# minimumSystem_Gustina_diah.net
KiCad netlist of a schematic drawn in EAGLE
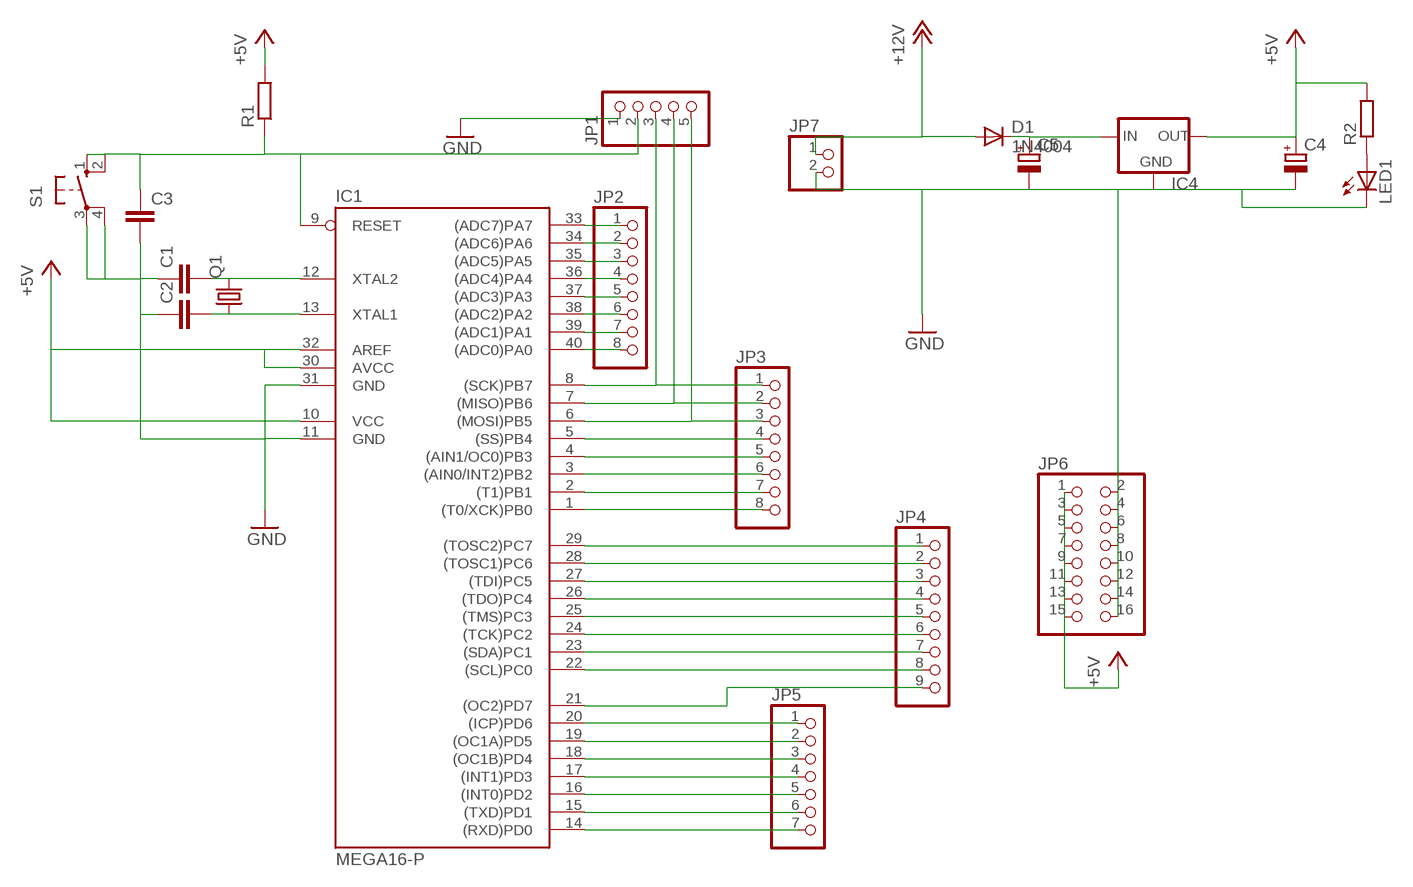
[diagram p0: schematic, sheet 1]

(export (version "E")
  (design (tool "Eeschema 10.0.6"))
  (components
    (comp (ref "C1")
      (value "C-EU025-024X044")
      (footprint "eagle-import:C025-024X044")
      (libsource (lib "eagle-import") (part "C-EU025-024X044"))
    )
    (comp (ref "C2")
      (value "C-EU025-024X044")
      (footprint "eagle-import:C025-024X044")
      (libsource (lib "eagle-import") (part "C-EU025-024X044"))
    )
    (comp (ref "C3")
      (value "C-EU050-025X075")
      (footprint "eagle-import:C050-025X075")
      (libsource (lib "eagle-import") (part "resistor_C-EU050-025X075"))
    )
    (comp (ref "C4")
      (value "CPOL-EUE2.5-5")
      (footprint "eagle-import:E2,5-5")
      (libsource (lib "eagle-import") (part "CPOL-EUE2.5-5"))
    )
    (comp (ref "C5")
      (value "CPOL-EUE2.5-5")
      (footprint "eagle-import:E2,5-5")
      (libsource (lib "eagle-import") (part "CPOL-EUE2.5-5"))
    )
    (comp (ref "D1")
      (value "1N4004")
      (footprint "eagle-import:DO41-10")
      (libsource (lib "eagle-import") (part "1N4004"))
    )
    (comp (ref "IC1")
      (value "MEGA16-P")
      (footprint "eagle-import:DIL40")
      (fields (field (name "MPN") "ATMEGA16-16PU"))
      (libsource (lib "eagle-import") (part "MEGA16-P"))
    )
    (comp (ref "IC4")
      (value "78XXS")
      (footprint "eagle-import:78XXS")
      (libsource (lib "eagle-import") (part "78XXS"))
    )
    (comp (ref "JP1")
      (value "PINHD-1X5")
      (footprint "eagle-import:1X05")
      (libsource (lib "eagle-import") (part "PINHD-1X5"))
    )
    (comp (ref "JP2")
      (value "PINHD-1X8")
      (footprint "eagle-import:1X08")
      (libsource (lib "eagle-import") (part "PINHD-1X8"))
    )
    (comp (ref "JP3")
      (value "PINHD-1X8")
      (footprint "eagle-import:1X08")
      (libsource (lib "eagle-import") (part "PINHD-1X8"))
    )
    (comp (ref "JP4")
      (value "PINHD-1X9")
      (footprint "eagle-import:1X09")
      (libsource (lib "eagle-import") (part "PINHD-1X9"))
    )
    (comp (ref "JP5")
      (value "PINHD-1X7")
      (footprint "eagle-import:1X07")
      (libsource (lib "eagle-import") (part "PINHD-1X7"))
    )
    (comp (ref "JP6")
      (value "PINHD-2X8")
      (footprint "eagle-import:2X08")
      (libsource (lib "eagle-import") (part "PINHD-2X8"))
    )
    (comp (ref "JP7")
      (value "PINHD-1X2")
      (footprint "eagle-import:1X02")
      (libsource (lib "eagle-import") (part "PINHD-1X2"))
    )
    (comp (ref "LED1")
      (value "LED5MM")
      (footprint "eagle-import:LED5MM")
      (libsource (lib "eagle-import") (part "LED5MM"))
    )
    (comp (ref "Q1")
      (value "CRYSTALHC49U-V")
      (footprint "eagle-import:HC49U-V")
      (libsource (lib "eagle-import") (part "CRYSTALHC49U-V"))
    )
    (comp (ref "R1")
      (value "R-EU_0204/7")
      (footprint "eagle-import:0204_7")
      (libsource (lib "eagle-import") (part "R-EU_0204/7"))
    )
    (comp (ref "R2")
      (value "R-EU_0204/7")
      (footprint "eagle-import:0204_7")
      (libsource (lib "eagle-import") (part "R-EU_0204/7"))
    )
    (comp (ref "S1")
      (value "10-XX")
      (footprint "eagle-import:B3F-10XX")
      (fields (field (name "MPN") "B3F-1000"))
      (libsource (lib "eagle-import") (part "10-XX"))
    )
  )
  (nets
    (net (code "1") (name "+5V") (class "Default")
      (node (ref "C4") (pin "+") (pinfunction "+_+") (pintype "passive"))
      (node (ref "IC1") (pin "10") (pinfunction "VCC_10") (pintype "power_in"))
      (node (ref "IC1") (pin "30") (pinfunction "AVCC_30") (pintype "power_in"))
      (node (ref "IC1") (pin "32") (pinfunction "AREF_32") (pintype "passive"))
      (node (ref "IC4") (pin "OUT") (pinfunction "OUT_OUT") (pintype "passive"))
      (node (ref "JP6") (pin "1") (pinfunction "1_1") (pintype "passive"))
      (node (ref "JP6") (pin "11") (pinfunction "11_11") (pintype "passive"))
      (node (ref "JP6") (pin "13") (pinfunction "13_13") (pintype "passive"))
      (node (ref "JP6") (pin "15") (pinfunction "15_15") (pintype "passive"))
      (node (ref "JP6") (pin "3") (pinfunction "3_3") (pintype "passive"))
      (node (ref "JP6") (pin "5") (pinfunction "5_5") (pintype "passive"))
      (node (ref "JP6") (pin "7") (pinfunction "7_7") (pintype "passive"))
      (node (ref "JP6") (pin "9") (pinfunction "9_9") (pintype "passive"))
      (node (ref "R1") (pin "2") (pinfunction "2_2") (pintype "passive"))
      (node (ref "R2") (pin "2") (pinfunction "2_2") (pintype "passive"))
    )
    (net (code "2") (name "+12V") (class "Default")
      (node (ref "D1") (pin "A") (pinfunction "A_A") (pintype "passive"))
      (node (ref "JP7") (pin "1") (pinfunction "1_1") (pintype "passive"))
    )
    (net (code "3") (name "GND") (class "Default")
      (node (ref "C1") (pin "1") (pinfunction "1_1") (pintype "passive"))
      (node (ref "C2") (pin "1") (pinfunction "1_1") (pintype "passive"))
      (node (ref "C3") (pin "2") (pinfunction "2_2") (pintype "passive"))
      (node (ref "C4") (pin "-") (pinfunction "-_-") (pintype "passive"))
      (node (ref "C5") (pin "-") (pinfunction "-_-") (pintype "passive"))
      (node (ref "IC1") (pin "11") (pinfunction "GND_11") (pintype "power_in"))
      (node (ref "IC1") (pin "31") (pinfunction "GND_31") (pintype "power_in"))
      (node (ref "IC4") (pin "GND") (pinfunction "GND_GND") (pintype "input"))
      (node (ref "JP1") (pin "1") (pinfunction "1_1") (pintype "passive"))
      (node (ref "JP6") (pin "10") (pinfunction "10_10") (pintype "passive"))
      (node (ref "JP6") (pin "12") (pinfunction "12_12") (pintype "passive"))
      (node (ref "JP6") (pin "14") (pinfunction "14_14") (pintype "passive"))
      (node (ref "JP6") (pin "16") (pinfunction "16_16") (pintype "passive"))
      (node (ref "JP6") (pin "2") (pinfunction "2_2") (pintype "passive"))
      (node (ref "JP6") (pin "4") (pinfunction "4_4") (pintype "passive"))
      (node (ref "JP6") (pin "6") (pinfunction "6_6") (pintype "passive"))
      (node (ref "JP6") (pin "8") (pinfunction "8_8") (pintype "passive"))
      (node (ref "JP7") (pin "2") (pinfunction "2_2") (pintype "passive"))
      (node (ref "LED1") (pin "K") (pinfunction "C_K") (pintype "passive"))
      (node (ref "S1") (pin "3") (pinfunction "P_3") (pintype "passive"))
      (node (ref "S1") (pin "4") (pinfunction "P1_4") (pintype "passive"))
    )
    (net (code "4") (name "Net-(C5-Pad+)") (class "Default")
      (node (ref "C5") (pin "+") (pinfunction "+_+") (pintype "passive"))
      (node (ref "D1") (pin "C") (pinfunction "C_C") (pintype "passive"))
      (node (ref "IC4") (pin "IN") (pinfunction "IN_IN") (pintype "input"))
    )
    (net (code "5") (name "Net-(IC1-(ADC0)PA0)") (class "Default")
      (node (ref "IC1") (pin "40") (pinfunction "(ADC0)PA0_40") (pintype "bidirectional"))
      (node (ref "JP2") (pin "8") (pinfunction "8_8") (pintype "passive"))
    )
    (net (code "6") (name "Net-(IC1-(ADC1)PA1)") (class "Default")
      (node (ref "IC1") (pin "39") (pinfunction "(ADC1)PA1_39") (pintype "bidirectional"))
      (node (ref "JP2") (pin "7") (pinfunction "7_7") (pintype "passive"))
    )
    (net (code "7") (name "Net-(IC1-(ADC2)PA2)") (class "Default")
      (node (ref "IC1") (pin "38") (pinfunction "(ADC2)PA2_38") (pintype "bidirectional"))
      (node (ref "JP2") (pin "6") (pinfunction "6_6") (pintype "passive"))
    )
    (net (code "8") (name "Net-(IC1-(ADC3)PA3)") (class "Default")
      (node (ref "IC1") (pin "37") (pinfunction "(ADC3)PA3_37") (pintype "bidirectional"))
      (node (ref "JP2") (pin "5") (pinfunction "5_5") (pintype "passive"))
    )
    (net (code "9") (name "Net-(IC1-(ADC4)PA4)") (class "Default")
      (node (ref "IC1") (pin "36") (pinfunction "(ADC4)PA4_36") (pintype "bidirectional"))
      (node (ref "JP2") (pin "4") (pinfunction "4_4") (pintype "passive"))
    )
    (net (code "10") (name "Net-(IC1-(ADC5)PA5)") (class "Default")
      (node (ref "IC1") (pin "35") (pinfunction "(ADC5)PA5_35") (pintype "bidirectional"))
      (node (ref "JP2") (pin "3") (pinfunction "3_3") (pintype "passive"))
    )
    (net (code "11") (name "Net-(IC1-(ADC6)PA6)") (class "Default")
      (node (ref "IC1") (pin "34") (pinfunction "(ADC6)PA6_34") (pintype "bidirectional"))
      (node (ref "JP2") (pin "2") (pinfunction "2_2") (pintype "passive"))
    )
    (net (code "12") (name "Net-(IC1-(ADC7)PA7)") (class "Default")
      (node (ref "IC1") (pin "33") (pinfunction "(ADC7)PA7_33") (pintype "bidirectional"))
      (node (ref "JP2") (pin "1") (pinfunction "1_1") (pintype "passive"))
    )
    (net (code "13") (name "Net-(IC1-(AIN0{slash}INT2)PB2)") (class "Default")
      (node (ref "IC1") (pin "3") (pinfunction "(AIN0/INT2)PB2_3") (pintype "bidirectional"))
      (node (ref "JP3") (pin "6") (pinfunction "6_6") (pintype "passive"))
    )
    (net (code "14") (name "Net-(IC1-(AIN1{slash}OC0)PB3)") (class "Default")
      (node (ref "IC1") (pin "4") (pinfunction "(AIN1/OC0)PB3_4") (pintype "bidirectional"))
      (node (ref "JP3") (pin "5") (pinfunction "5_5") (pintype "passive"))
    )
    (net (code "15") (name "Net-(IC1-(ICP)PD6)") (class "Default")
      (node (ref "IC1") (pin "20") (pinfunction "(ICP)PD6_20") (pintype "bidirectional"))
      (node (ref "JP5") (pin "1") (pinfunction "1_1") (pintype "passive"))
    )
    (net (code "16") (name "Net-(IC1-(INT0)PD2)") (class "Default")
      (node (ref "IC1") (pin "16") (pinfunction "(INT0)PD2_16") (pintype "bidirectional"))
      (node (ref "JP5") (pin "5") (pinfunction "5_5") (pintype "passive"))
    )
    (net (code "17") (name "Net-(IC1-(INT1)PD3)") (class "Default")
      (node (ref "IC1") (pin "17") (pinfunction "(INT1)PD3_17") (pintype "bidirectional"))
      (node (ref "JP5") (pin "4") (pinfunction "4_4") (pintype "passive"))
    )
    (net (code "18") (name "Net-(IC1-(MISO)PB6)") (class "Default")
      (node (ref "IC1") (pin "7") (pinfunction "(MISO)PB6_7") (pintype "bidirectional"))
      (node (ref "JP1") (pin "4") (pinfunction "4_4") (pintype "passive"))
      (node (ref "JP3") (pin "2") (pinfunction "2_2") (pintype "passive"))
    )
    (net (code "19") (name "Net-(IC1-(MOSI)PB5)") (class "Default")
      (node (ref "IC1") (pin "6") (pinfunction "(MOSI)PB5_6") (pintype "bidirectional"))
      (node (ref "JP1") (pin "5") (pinfunction "5_5") (pintype "passive"))
      (node (ref "JP3") (pin "3") (pinfunction "3_3") (pintype "passive"))
    )
    (net (code "20") (name "Net-(IC1-(OC1A)PD5)") (class "Default")
      (node (ref "IC1") (pin "19") (pinfunction "(OC1A)PD5_19") (pintype "bidirectional"))
      (node (ref "JP5") (pin "2") (pinfunction "2_2") (pintype "passive"))
    )
    (net (code "21") (name "Net-(IC1-(OC1B)PD4)") (class "Default")
      (node (ref "IC1") (pin "18") (pinfunction "(OC1B)PD4_18") (pintype "bidirectional"))
      (node (ref "JP5") (pin "3") (pinfunction "3_3") (pintype "passive"))
    )
    (net (code "22") (name "Net-(IC1-(OC2)PD7)") (class "Default")
      (node (ref "IC1") (pin "21") (pinfunction "(OC2)PD7_21") (pintype "bidirectional"))
      (node (ref "JP4") (pin "9") (pinfunction "9_9") (pintype "passive"))
    )
    (net (code "23") (name "Net-(IC1-(RXD)PD0)") (class "Default")
      (node (ref "IC1") (pin "14") (pinfunction "(RXD)PD0_14") (pintype "bidirectional"))
      (node (ref "JP5") (pin "7") (pinfunction "7_7") (pintype "passive"))
    )
    (net (code "24") (name "Net-(IC1-(SCK)PB7)") (class "Default")
      (node (ref "IC1") (pin "8") (pinfunction "(SCK)PB7_8") (pintype "bidirectional"))
      (node (ref "JP1") (pin "3") (pinfunction "3_3") (pintype "passive"))
      (node (ref "JP3") (pin "1") (pinfunction "1_1") (pintype "passive"))
    )
    (net (code "25") (name "Net-(IC1-(SCL)PC0)") (class "Default")
      (node (ref "IC1") (pin "22") (pinfunction "(SCL)PC0_22") (pintype "bidirectional"))
      (node (ref "JP4") (pin "8") (pinfunction "8_8") (pintype "passive"))
    )
    (net (code "26") (name "Net-(IC1-(SDA)PC1)") (class "Default")
      (node (ref "IC1") (pin "23") (pinfunction "(SDA)PC1_23") (pintype "bidirectional"))
      (node (ref "JP4") (pin "7") (pinfunction "7_7") (pintype "passive"))
    )
    (net (code "27") (name "Net-(IC1-(SS)PB4)") (class "Default")
      (node (ref "IC1") (pin "5") (pinfunction "(SS)PB4_5") (pintype "bidirectional"))
      (node (ref "JP3") (pin "4") (pinfunction "4_4") (pintype "passive"))
    )
    (net (code "28") (name "Net-(IC1-(T0{slash}XCK)PB0)") (class "Default")
      (node (ref "IC1") (pin "1") (pinfunction "(T0/XCK)PB0_1") (pintype "bidirectional"))
      (node (ref "JP3") (pin "8") (pinfunction "8_8") (pintype "passive"))
    )
    (net (code "29") (name "Net-(IC1-(T1)PB1)") (class "Default")
      (node (ref "IC1") (pin "2") (pinfunction "(T1)PB1_2") (pintype "bidirectional"))
      (node (ref "JP3") (pin "7") (pinfunction "7_7") (pintype "passive"))
    )
    (net (code "30") (name "Net-(IC1-(TCK)PC2)") (class "Default")
      (node (ref "IC1") (pin "24") (pinfunction "(TCK)PC2_24") (pintype "bidirectional"))
      (node (ref "JP4") (pin "6") (pinfunction "6_6") (pintype "passive"))
    )
    (net (code "31") (name "Net-(IC1-(TDI)PC5)") (class "Default")
      (node (ref "IC1") (pin "27") (pinfunction "(TDI)PC5_27") (pintype "bidirectional"))
      (node (ref "JP4") (pin "3") (pinfunction "3_3") (pintype "passive"))
    )
    (net (code "32") (name "Net-(IC1-(TDO)PC4)") (class "Default")
      (node (ref "IC1") (pin "26") (pinfunction "(TDO)PC4_26") (pintype "bidirectional"))
      (node (ref "JP4") (pin "4") (pinfunction "4_4") (pintype "passive"))
    )
    (net (code "33") (name "Net-(IC1-(TMS)PC3)") (class "Default")
      (node (ref "IC1") (pin "25") (pinfunction "(TMS)PC3_25") (pintype "bidirectional"))
      (node (ref "JP4") (pin "5") (pinfunction "5_5") (pintype "passive"))
    )
    (net (code "34") (name "Net-(IC1-(TOSC1)PC6)") (class "Default")
      (node (ref "IC1") (pin "28") (pinfunction "(TOSC1)PC6_28") (pintype "bidirectional"))
      (node (ref "JP4") (pin "2") (pinfunction "2_2") (pintype "passive"))
    )
    (net (code "35") (name "Net-(IC1-(TOSC2)PC7)") (class "Default")
      (node (ref "IC1") (pin "29") (pinfunction "(TOSC2)PC7_29") (pintype "bidirectional"))
      (node (ref "JP4") (pin "1") (pinfunction "1_1") (pintype "passive"))
    )
    (net (code "36") (name "Net-(IC1-(TXD)PD1)") (class "Default")
      (node (ref "IC1") (pin "15") (pinfunction "(TXD)PD1_15") (pintype "bidirectional"))
      (node (ref "JP5") (pin "6") (pinfunction "6_6") (pintype "passive"))
    )
    (net (code "37") (name "Net-(IC1-RESET)") (class "Default")
      (node (ref "C3") (pin "1") (pinfunction "1_1") (pintype "passive"))
      (node (ref "IC1") (pin "9") (pinfunction "RESET_9") (pintype "input"))
      (node (ref "JP1") (pin "2") (pinfunction "2_2") (pintype "passive"))
      (node (ref "R1") (pin "1") (pinfunction "1_1") (pintype "passive"))
      (node (ref "S1") (pin "1") (pinfunction "S_1") (pintype "passive"))
      (node (ref "S1") (pin "2") (pinfunction "S1_2") (pintype "passive"))
    )
    (net (code "38") (name "Net-(IC1-XTAL1)") (class "Default")
      (node (ref "C2") (pin "2") (pinfunction "2_2") (pintype "passive"))
      (node (ref "IC1") (pin "13") (pinfunction "XTAL1_13") (pintype "bidirectional"))
      (node (ref "Q1") (pin "1") (pinfunction "1_1") (pintype "passive"))
    )
    (net (code "39") (name "Net-(IC1-XTAL2)") (class "Default")
      (node (ref "C1") (pin "2") (pinfunction "2_2") (pintype "passive"))
      (node (ref "IC1") (pin "12") (pinfunction "XTAL2_12") (pintype "bidirectional"))
      (node (ref "Q1") (pin "2") (pinfunction "2_2") (pintype "passive"))
    )
    (net (code "40") (name "Net-(LED1-PadA)") (class "Default")
      (node (ref "LED1") (pin "A") (pinfunction "A_A") (pintype "passive"))
      (node (ref "R2") (pin "1") (pinfunction "1_1") (pintype "passive"))
    )
  )
)
